# hvsp.net
KiCad netlist of a schematic drawn in EAGLE
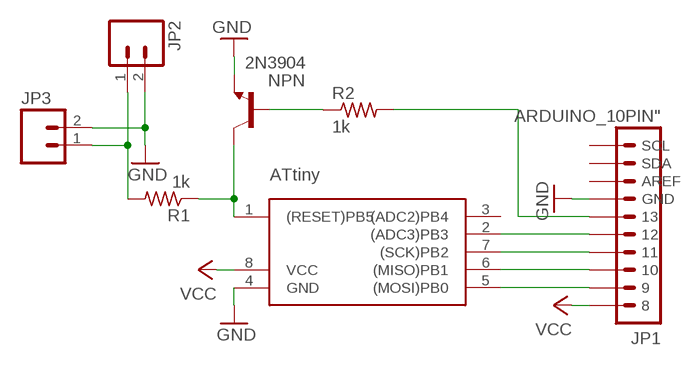
[diagram p0: schematic, sheet 1]

(export (version "E")
  (design (tool "Eeschema 10.0.6"))
  (components
    (comp (ref "JP1")
      (value "ARDUINO_10PIN\"")
      (footprint "eagle-import:ARDUINO_10PIN")
      (libsource (lib "eagle-import") (part "ARDUINO_10PIN{dblquote}"))
    )
    (comp (ref "JP2")
      (value "M025MM")
      (footprint "eagle-import:SCREWTERMINAL-5MM-2")
      (libsource (lib "eagle-import") (part "M025MM"))
    )
    (comp (ref "JP3")
      (value "M021X02_NO_SILK")
      (footprint "eagle-import:1X02_NO_SILK")
      (libsource (lib "eagle-import") (part "M021X02_NO_SILK"))
    )
    (comp (ref "NPN")
      (value "2N3904")
      (footprint "eagle-import:TO92")
      (libsource (lib "eagle-import") (part "2N3904"))
    )
    (comp (ref "R1")
      (value "1k")
      (footprint "eagle-import:0204_7")
      (libsource (lib "eagle-import") (part "R-US_0204/7"))
    )
    (comp (ref "R2")
      (value "1k")
      (footprint "eagle-import:0204_7")
      (libsource (lib "eagle-import") (part "R-US_0204/7"))
    )
    (comp (ref "U$2")
      (value "ATtiny")
      (footprint "eagle-import:AVR-7_DIL08")
      (libsource (lib "eagle-import") (part "ATTINY858P3"))
    )
  )
  (nets
    (net (code "1") (name "GND") (class "Default")
      (node (ref "JP1") (pin "4") (pinfunction "GND_4") (pintype "passive"))
      (node (ref "JP2") (pin "2") (pinfunction "2_2") (pintype "passive"))
      (node (ref "JP3") (pin "2") (pinfunction "2_2") (pintype "passive"))
      (node (ref "NPN") (pin "3") (pinfunction "E_3") (pintype "passive"))
      (node (ref "U$2") (pin "4") (pinfunction "GND_4") (pintype "power_in"))
    )
    (net (code "2") (name "Net-(JP1-10)") (class "Default")
      (node (ref "JP1") (pin "8") (pinfunction "10_8") (pintype "passive"))
      (node (ref "U$2") (pin "6") (pinfunction "(MISO)PB1_6") (pintype "bidirectional"))
    )
    (net (code "3") (name "Net-(JP1-11)") (class "Default")
      (node (ref "JP1") (pin "7") (pinfunction "11_7") (pintype "passive"))
      (node (ref "U$2") (pin "7") (pinfunction "(SCK)PB2_7") (pintype "bidirectional"))
    )
    (net (code "4") (name "Net-(JP1-12)") (class "Default")
      (node (ref "JP1") (pin "6") (pinfunction "12_6") (pintype "passive"))
      (node (ref "U$2") (pin "2") (pinfunction "(ADC3)PB3_2") (pintype "bidirectional"))
    )
    (net (code "5") (name "Net-(JP1-13)") (class "Default")
      (node (ref "JP1") (pin "5") (pinfunction "13_5") (pintype "passive"))
      (node (ref "R2") (pin "2") (pinfunction "2_2") (pintype "passive"))
    )
    (net (code "6") (name "Net-(JP2-Pad1)") (class "Default")
      (node (ref "JP2") (pin "1") (pinfunction "1_1") (pintype "passive"))
      (node (ref "JP3") (pin "1") (pinfunction "1_1") (pintype "passive"))
      (node (ref "R1") (pin "2") (pinfunction "2_2") (pintype "passive"))
    )
    (net (code "7") (name "Net-(NPN-B)") (class "Default")
      (node (ref "NPN") (pin "2") (pinfunction "B_2") (pintype "passive"))
      (node (ref "R2") (pin "1") (pinfunction "1_1") (pintype "passive"))
    )
    (net (code "8") (name "Net-(NPN-C)") (class "Default")
      (node (ref "NPN") (pin "1") (pinfunction "C_1") (pintype "passive"))
      (node (ref "R1") (pin "1") (pinfunction "1_1") (pintype "passive"))
      (node (ref "U$2") (pin "1") (pinfunction "(RESET)PB5_1") (pintype "bidirectional"))
    )
    (net (code "9") (name "Net-(U$2-(MOSI)PB0)") (class "Default")
      (node (ref "JP1") (pin "9") (pinfunction "9_9") (pintype "passive"))
      (node (ref "U$2") (pin "5") (pinfunction "(MOSI)PB0_5") (pintype "bidirectional"))
    )
    (net (code "10") (name "VCC") (class "Default")
      (node (ref "JP1") (pin "10") (pinfunction "8_10") (pintype "passive"))
      (node (ref "U$2") (pin "8") (pinfunction "VCC_8") (pintype "power_in"))
    )
    (net (code "11") (name "unconnected-(JP1-AREF-Pad3)") (class "Default")
      (node (ref "JP1") (pin "3") (pinfunction "AREF_3") (pintype "passive"))
    )
    (net (code "12") (name "unconnected-(JP1-SCL-Pad1)") (class "Default")
      (node (ref "JP1") (pin "1") (pinfunction "SCL_1") (pintype "passive"))
    )
    (net (code "13") (name "unconnected-(JP1-SDA-Pad2)") (class "Default")
      (node (ref "JP1") (pin "2") (pinfunction "SDA_2") (pintype "passive"))
    )
    (net (code "14") (name "unconnected-(U$2-(ADC2)PB4-Pad3)") (class "Default")
      (node (ref "U$2") (pin "3") (pinfunction "(ADC2)PB4_3") (pintype "bidirectional"))
    )
  )
)
